# untitled.net
KiCad netlist of a schematic drawn in EAGLE
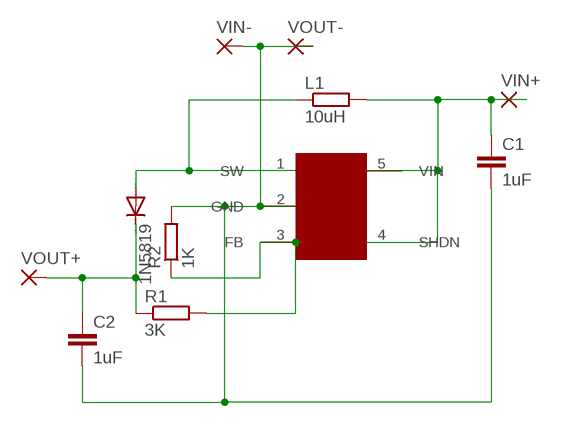
[diagram p0: schematic, sheet 1]

(export (version "E")
  (design (tool "Eeschema 10.0.6"))
  (components
    (comp (ref "1N5819")
      (value "DIODE-DO214AC")
      (footprint "eagle-import:DO214AC")
      (libsource (lib "eagle-import") (part "DIODE-DO214AC"))
    )
    (comp (ref "C1")
      (value "1uF")
      (footprint "eagle-import:C1206")
      (libsource (lib "eagle-import") (part "C-EUC1206"))
    )
    (comp (ref "C2")
      (value "1uF")
      (footprint "eagle-import:C1206")
      (libsource (lib "eagle-import") (part "C-EUC1206"))
    )
    (comp (ref "L1")
      (value "10uH")
      (footprint "eagle-import:R0805")
      (libsource (lib "eagle-import") (part "R-EU_R0805"))
    )
    (comp (ref "R1")
      (value "3K")
      (footprint "eagle-import:R1206")
      (libsource (lib "eagle-import") (part "R-EU_R1206"))
    )
    (comp (ref "R2")
      (value "1K")
      (footprint "eagle-import:R1206")
      (libsource (lib "eagle-import") (part "R-EU_R1206"))
    )
    (comp (ref "U$8")
      (value "AP3012")
      (footprint "eagle-import:SOT-23-5")
      (libsource (lib "eagle-import") (part "AP3012"))
    )
    (comp (ref "VIN+")
      (value "SMD2")
      (footprint "eagle-import:SMD1,27-2,54")
      (libsource (lib "eagle-import") (part "SMD2"))
    )
    (comp (ref "VIN-")
      (value "SMD2")
      (footprint "eagle-import:SMD1,27-2,54")
      (libsource (lib "eagle-import") (part "SMD2"))
    )
    (comp (ref "VOUT+")
      (value "SMD2")
      (footprint "eagle-import:SMD1,27-2,54")
      (libsource (lib "eagle-import") (part "SMD2"))
    )
    (comp (ref "VOUT-")
      (value "SMD2")
      (footprint "eagle-import:SMD1,27-2,54")
      (libsource (lib "eagle-import") (part "SMD2"))
    )
  )
  (nets
    (net (code "1") (name "Net-(U$8-FB)") (class "Default")
      (node (ref "R1") (pin "2") (pinfunction "2_2") (pintype "passive"))
      (node (ref "R2") (pin "1") (pinfunction "1_1") (pintype "passive"))
      (node (ref "U$8") (pin "3") (pinfunction "FB_3") (pintype "bidirectional"))
    )
    (net (code "2") (name "Net-(U$8-GND)") (class "Default")
      (node (ref "C1") (pin "2") (pinfunction "2_2") (pintype "passive"))
      (node (ref "C2") (pin "2") (pinfunction "2_2") (pintype "passive"))
      (node (ref "R2") (pin "2") (pinfunction "2_2") (pintype "passive"))
      (node (ref "U$8") (pin "2") (pinfunction "GND_2") (pintype "bidirectional"))
      (node (ref "VIN-") (pin "1") (pinfunction "P_1") (pintype "passive"))
      (node (ref "VOUT-") (pin "1") (pinfunction "P_1") (pintype "passive"))
    )
    (net (code "3") (name "Net-(U$8-SHDN)") (class "Default")
      (node (ref "C1") (pin "1") (pinfunction "1_1") (pintype "passive"))
      (node (ref "L1") (pin "2") (pinfunction "2_2") (pintype "passive"))
      (node (ref "U$8") (pin "4") (pinfunction "SHDN_4") (pintype "bidirectional"))
      (node (ref "U$8") (pin "5") (pinfunction "VIN_5") (pintype "bidirectional"))
      (node (ref "VIN+") (pin "1") (pinfunction "P_1") (pintype "passive"))
    )
    (net (code "4") (name "Net-(U$8-SW)") (class "Default")
      (node (ref "1N5819") (pin "A") (pinfunction "A_A") (pintype "passive"))
      (node (ref "L1") (pin "1") (pinfunction "1_1") (pintype "passive"))
      (node (ref "U$8") (pin "1") (pinfunction "SW_1") (pintype "bidirectional"))
    )
    (net (code "5") (name "Net-(VOUT+-P)") (class "Default")
      (node (ref "1N5819") (pin "C") (pinfunction "C_C") (pintype "passive"))
      (node (ref "C2") (pin "1") (pinfunction "1_1") (pintype "passive"))
      (node (ref "R1") (pin "1") (pinfunction "1_1") (pintype "passive"))
      (node (ref "VOUT+") (pin "1") (pinfunction "P_1") (pintype "passive"))
    )
  )
)
